# PowerSupply.net
KiCad netlist of a schematic drawn in Altium Designer
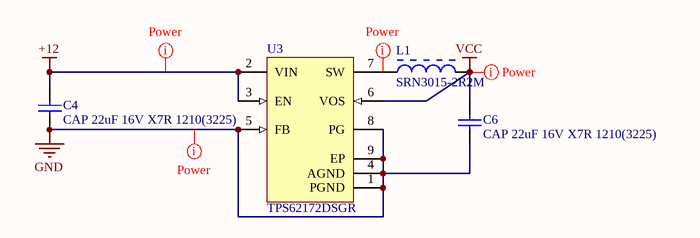
[diagram p0: PowerSupply.SchDoc]

(export (version "E")
  (design (tool "Eeschema 10.0.6"))
  (components
    (comp (ref "C4")
      (value "CAP 22uF 16V X7R 1210(3225)")
      (footprint "CAPC1210(3225)280_L")
      (description "CAP 22uF 16V ±10% 1210 (3225 Metric) Thickness 2.8mm SMD")
      (fields (field (name "TOLERANCE") "Â±10%"))
      (libsource (lib "") (part "CAP_1"))
    )
    (comp (ref "C6")
      (value "CAP 22uF 16V X7R 1210(3225)")
      (footprint "CAPC1210(3225)280_L")
      (description "CAP 22uF 16V ±10% 1210 (3225 Metric) Thickness 2.8mm SMD")
      (fields (field (name "TOLERANCE") "Â±10%"))
      (libsource (lib "Altium Content Vault") (part "CAP"))
    )
    (comp (ref "L1")
      (value "SRN3015-2R2M")
      (footprint "BOUR-SRN3015-2_V")
      (fields (field (name "MANUFACTURER") "Bourns"))
      (libsource (lib "Altium Content Vault") (part "BOUR-IND-2A"))
    )
    (comp (ref "U3")
      (value "TPS62172DSGR")
      (footprint "DSG8-1600X900TP")
      (fields (field (name "MANUFACTURER") "Texas Instruments"))
      (libsource (lib "Texas_Instruments_TPS62172DSGR") (part "TPS62172DSGR"))
    )
  )
  (nets
    (net (code "1") (name "+12") (class "Default")
      (node (ref "C4") (pin "2") (pinfunction "2_2") (pintype "passive"))
      (node (ref "U3") (pin "2") (pinfunction "VIN_2") (pintype "power_in"))
      (node (ref "U3") (pin "3") (pinfunction "EN_3") (pintype "input"))
    )
    (net (code "2") (name "GND") (class "Default")
      (node (ref "C4") (pin "1") (pinfunction "1_1") (pintype "passive"))
      (node (ref "C6") (pin "1") (pinfunction "1_1") (pintype "passive"))
      (node (ref "U3") (pin "1") (pinfunction "PGND_1") (pintype "power_in"))
      (node (ref "U3") (pin "4") (pinfunction "AGND_4") (pintype "power_in"))
      (node (ref "U3") (pin "5") (pinfunction "FB_5") (pintype "input"))
      (node (ref "U3") (pin "8") (pinfunction "PG_8") (pintype "passive"))
      (node (ref "U3") (pin "9") (pinfunction "EP_9") (pintype "power_in"))
    )
    (net (code "3") (name "Net-(U3-SW)") (class "Default")
      (node (ref "L1") (pin "1") (pinfunction "1_1") (pintype "passive"))
      (node (ref "U3") (pin "7") (pinfunction "SW_7") (pintype "power_in"))
    )
    (net (code "4") (name "VCC") (class "Default")
      (node (ref "C6") (pin "2") (pinfunction "2_2") (pintype "passive"))
      (node (ref "L1") (pin "2") (pinfunction "2_2") (pintype "passive"))
      (node (ref "U3") (pin "6") (pinfunction "VOS_6") (pintype "input"))
    )
  )
)
